# QCopterRC_MCU_Sch.net
KiCad netlist of a schematic drawn in Altium Designer
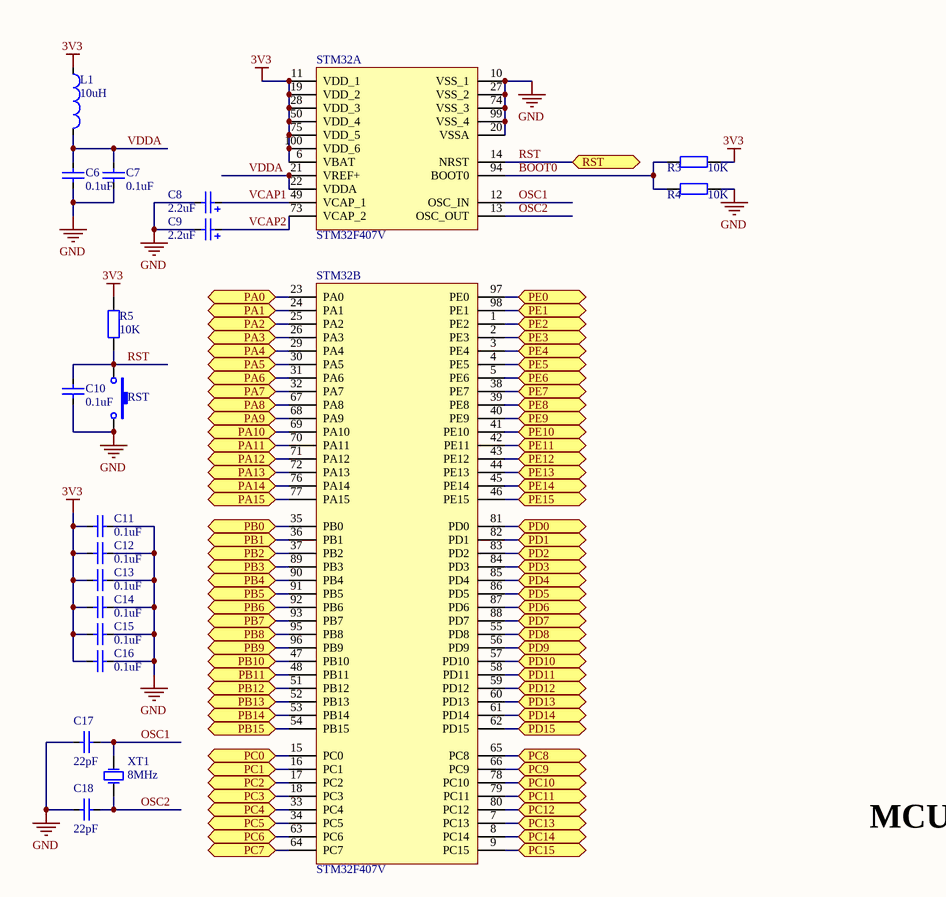
[diagram p0: QCopterRC_MCU_Sch.SchDoc]

(export (version "E")
  (design (tool "Eeschema 10.0.6"))
  (components
    (comp (ref "C6")
      (value "0.1uF")
      (footprint "PCB_Passive:CAP_0603")
      (description "Capacitor")
      (fields (field (name "Comment") "Cap_0603"))
      (libsource (lib "SCH_Passive") (part "Cap_0603"))
    )
    (comp (ref "C7")
      (value "0.1uF")
      (footprint "PCB_Passive:CAP_0603")
      (description "Capacitor")
      (fields (field (name "Comment") "Cap_0603"))
      (libsource (lib "SCH_Passive") (part "Cap_0603"))
    )
    (comp (ref "C8")
      (value "2.2uF")
      (footprint "PCB_Passive:CAP_TAN_P0805")
      (description "Capacitor")
      (fields (field (name "Comment") "Cap_Tan_0805"))
      (libsource (lib "SCH_Passive") (part "Cap_Tan_0805"))
    )
    (comp (ref "C9")
      (value "2.2uF")
      (footprint "PCB_Passive:CAP_TAN_P0805")
      (description "Capacitor")
      (fields (field (name "Comment") "Cap_Tan_0805"))
      (libsource (lib "SCH_Passive") (part "Cap_Tan_0805"))
    )
    (comp (ref "C10")
      (value "0.1uF")
      (footprint "PCB_Passive:CAP_0603")
      (description "Capacitor")
      (fields (field (name "Comment") "Cap_0603"))
      (libsource (lib "SCH_Passive") (part "Cap_0603"))
    )
    (comp (ref "C11")
      (value "0.1uF")
      (footprint "PCB_Passive:CAP_0603")
      (description "Capacitor")
      (fields (field (name "Comment") "Cap_0603"))
      (libsource (lib "SCH_Passive") (part "Cap_0603"))
    )
    (comp (ref "C12")
      (value "0.1uF")
      (footprint "PCB_Passive:CAP_0603")
      (description "Capacitor")
      (fields (field (name "Comment") "Cap_0603"))
      (libsource (lib "SCH_Passive") (part "Cap_0603"))
    )
    (comp (ref "C13")
      (value "0.1uF")
      (footprint "PCB_Passive:CAP_0603")
      (description "Capacitor")
      (fields (field (name "Comment") "Cap_0603"))
      (libsource (lib "SCH_Passive") (part "Cap_0603"))
    )
    (comp (ref "C14")
      (value "0.1uF")
      (footprint "PCB_Passive:CAP_0603")
      (description "Capacitor")
      (fields (field (name "Comment") "Cap_0603"))
      (libsource (lib "SCH_Passive") (part "Cap_0603"))
    )
    (comp (ref "C15")
      (value "0.1uF")
      (footprint "PCB_Passive:CAP_0603")
      (description "Capacitor")
      (fields (field (name "Comment") "Cap_0603"))
      (libsource (lib "SCH_Passive") (part "Cap_0603"))
    )
    (comp (ref "C16")
      (value "0.1uF")
      (footprint "PCB_Passive:CAP_0603")
      (description "Capacitor")
      (fields (field (name "Comment") "Cap_0603"))
      (libsource (lib "SCH_Passive") (part "Cap_0603"))
    )
    (comp (ref "C17")
      (value "22pF")
      (footprint "PCB_Passive:CAP_0603")
      (description "Capacitor")
      (fields (field (name "Comment") "Cap_0603"))
      (libsource (lib "SCH_Passive") (part "Cap_0603"))
    )
    (comp (ref "C18")
      (value "22pF")
      (footprint "PCB_Passive:CAP_0603")
      (description "Capacitor")
      (fields (field (name "Comment") "Cap_0603"))
      (libsource (lib "SCH_Passive") (part "Cap_0603"))
    )
    (comp (ref "L1")
      (value "10uH")
      (footprint "PCB_Passive:IND_0603")
      (description "Inductor")
      (fields (field (name "Comment") "Ind_0603"))
      (libsource (lib "SCH_Passive") (part "Ind_0603"))
    )
    (comp (ref "R3")
      (value "10K")
      (footprint "PCB_Passive:RES_0603")
      (description "Resistor")
      (fields (field (name "Comment") "Res_0603"))
      (libsource (lib "") (part "Res_0603_1"))
    )
    (comp (ref "R4")
      (value "10K")
      (footprint "PCB_Passive:RES_0603")
      (description "Resistor")
      (fields (field (name "Comment") "Res_0603"))
      (libsource (lib "") (part "Res_0603_1"))
    )
    (comp (ref "R5")
      (value "10K")
      (footprint "PCB_Passive:RES_0603")
      (description "Resistor")
      (fields (field (name "Comment") "Res_0603"))
      (libsource (lib "SCH_Passive") (part "Res_0603"))
    )
    (comp (ref "RST")
      (value "BT_TACT_3x6_180")
      (footprint "PCB_Switch:BT_TACT_3x6_180")
      (description "Switch")
      (libsource (lib "SCH_Switch") (part "BT_TACT_3x6_180"))
    )
    (comp (ref "STM32")
      (value "STM32F407V")
      (footprint "PCB_IC:STM32F_100")
      (description "MCU")
      (libsource (lib "SCH_IC") (part "STM32F407V"))
    )
    (comp (ref "XT1")
      (value "8MHz")
      (footprint "PCB_Oscillator:XTAL_5032")
      (description "Crystal Oscillator")
      (fields (field (name "Comment") "XTAL_5032") (field (name "PUBLISHER") "Altium Limited"))
      (libsource (lib "SCH_Oscillator") (part "XTAL_5032"))
    )
  )
  (nets
    (net (code "1") (name "/BOOT0") (class "Default")
      (node (ref "R3") (pin "1") (pinfunction "1_1") (pintype "passive"))
      (node (ref "R4") (pin "1") (pinfunction "1_1") (pintype "passive"))
      (node (ref "STM32") (pin "94") (pinfunction "BOOT0_94") (pintype "passive"))
    )
    (net (code "2") (name "/OSC1") (class "Default")
      (node (ref "C17") (pin "2") (pinfunction "2_2") (pintype "passive"))
      (node (ref "STM32") (pin "12") (pinfunction "OSC_IN_12") (pintype "passive"))
      (node (ref "XT1") (pin "2") (pinfunction "OSC2_2") (pintype "passive"))
    )
    (net (code "3") (name "/OSC2") (class "Default")
      (node (ref "C18") (pin "2") (pinfunction "2_2") (pintype "passive"))
      (node (ref "STM32") (pin "13") (pinfunction "OSC_OUT_13") (pintype "passive"))
      (node (ref "XT1") (pin "1") (pinfunction "OSC1_1") (pintype "passive"))
    )
    (net (code "4") (name "/PA0") (class "Default")
      (node (ref "STM32") (pin "23") (pinfunction "PA0_23") (pintype "passive"))
    )
    (net (code "5") (name "/PA1") (class "Default")
      (node (ref "STM32") (pin "24") (pinfunction "PA1_24") (pintype "passive"))
    )
    (net (code "6") (name "/PA2") (class "Default")
      (node (ref "STM32") (pin "25") (pinfunction "PA2_25") (pintype "passive"))
    )
    (net (code "7") (name "/PA3") (class "Default")
      (node (ref "STM32") (pin "26") (pinfunction "PA3_26") (pintype "passive"))
    )
    (net (code "8") (name "/PA4") (class "Default")
      (node (ref "STM32") (pin "29") (pinfunction "PA4_29") (pintype "passive"))
    )
    (net (code "9") (name "/PA5") (class "Default")
      (node (ref "STM32") (pin "30") (pinfunction "PA5_30") (pintype "passive"))
    )
    (net (code "10") (name "/PA6") (class "Default")
      (node (ref "STM32") (pin "31") (pinfunction "PA6_31") (pintype "passive"))
    )
    (net (code "11") (name "/PA7") (class "Default")
      (node (ref "STM32") (pin "32") (pinfunction "PA7_32") (pintype "passive"))
    )
    (net (code "12") (name "/PA8") (class "Default")
      (node (ref "STM32") (pin "67") (pinfunction "PA8_67") (pintype "passive"))
    )
    (net (code "13") (name "/PA9") (class "Default")
      (node (ref "STM32") (pin "68") (pinfunction "PA9_68") (pintype "passive"))
    )
    (net (code "14") (name "/PA10") (class "Default")
      (node (ref "STM32") (pin "69") (pinfunction "PA10_69") (pintype "passive"))
    )
    (net (code "15") (name "/PA11") (class "Default")
      (node (ref "STM32") (pin "70") (pinfunction "PA11_70") (pintype "passive"))
    )
    (net (code "16") (name "/PA12") (class "Default")
      (node (ref "STM32") (pin "71") (pinfunction "PA12_71") (pintype "passive"))
    )
    (net (code "17") (name "/PA13") (class "Default")
      (node (ref "STM32") (pin "72") (pinfunction "PA13_72") (pintype "passive"))
    )
    (net (code "18") (name "/PA14") (class "Default")
      (node (ref "STM32") (pin "76") (pinfunction "PA14_76") (pintype "passive"))
    )
    (net (code "19") (name "/PA15") (class "Default")
      (node (ref "STM32") (pin "77") (pinfunction "PA15_77") (pintype "passive"))
    )
    (net (code "20") (name "/PB0") (class "Default")
      (node (ref "STM32") (pin "35") (pinfunction "PB0_35") (pintype "passive"))
    )
    (net (code "21") (name "/PB1") (class "Default")
      (node (ref "STM32") (pin "36") (pinfunction "PB1_36") (pintype "passive"))
    )
    (net (code "22") (name "/PB2") (class "Default")
      (node (ref "STM32") (pin "37") (pinfunction "PB2_37") (pintype "passive"))
    )
    (net (code "23") (name "/PB3") (class "Default")
      (node (ref "STM32") (pin "89") (pinfunction "PB3_89") (pintype "passive"))
    )
    (net (code "24") (name "/PB4") (class "Default")
      (node (ref "STM32") (pin "90") (pinfunction "PB4_90") (pintype "passive"))
    )
    (net (code "25") (name "/PB5") (class "Default")
      (node (ref "STM32") (pin "91") (pinfunction "PB5_91") (pintype "passive"))
    )
    (net (code "26") (name "/PB6") (class "Default")
      (node (ref "STM32") (pin "92") (pinfunction "PB6_92") (pintype "passive"))
    )
    (net (code "27") (name "/PB7") (class "Default")
      (node (ref "STM32") (pin "93") (pinfunction "PB7_93") (pintype "passive"))
    )
    (net (code "28") (name "/PB8") (class "Default")
      (node (ref "STM32") (pin "95") (pinfunction "PB8_95") (pintype "passive"))
    )
    (net (code "29") (name "/PB9") (class "Default")
      (node (ref "STM32") (pin "96") (pinfunction "PB9_96") (pintype "passive"))
    )
    (net (code "30") (name "/PB10") (class "Default")
      (node (ref "STM32") (pin "47") (pinfunction "PB10_47") (pintype "passive"))
    )
    (net (code "31") (name "/PB11") (class "Default")
      (node (ref "STM32") (pin "48") (pinfunction "PB11_48") (pintype "passive"))
    )
    (net (code "32") (name "/PB12") (class "Default")
      (node (ref "STM32") (pin "51") (pinfunction "PB12_51") (pintype "passive"))
    )
    (net (code "33") (name "/PB13") (class "Default")
      (node (ref "STM32") (pin "52") (pinfunction "PB13_52") (pintype "passive"))
    )
    (net (code "34") (name "/PB14") (class "Default")
      (node (ref "STM32") (pin "53") (pinfunction "PB14_53") (pintype "passive"))
    )
    (net (code "35") (name "/PB15") (class "Default")
      (node (ref "STM32") (pin "54") (pinfunction "PB15_54") (pintype "passive"))
    )
    (net (code "36") (name "/PC0") (class "Default")
      (node (ref "STM32") (pin "15") (pinfunction "PC0_15") (pintype "passive"))
    )
    (net (code "37") (name "/PC1") (class "Default")
      (node (ref "STM32") (pin "16") (pinfunction "PC1_16") (pintype "passive"))
    )
    (net (code "38") (name "/PC2") (class "Default")
      (node (ref "STM32") (pin "17") (pinfunction "PC2_17") (pintype "passive"))
    )
    (net (code "39") (name "/PC3") (class "Default")
      (node (ref "STM32") (pin "18") (pinfunction "PC3_18") (pintype "passive"))
    )
    (net (code "40") (name "/PC4") (class "Default")
      (node (ref "STM32") (pin "33") (pinfunction "PC4_33") (pintype "passive"))
    )
    (net (code "41") (name "/PC5") (class "Default")
      (node (ref "STM32") (pin "34") (pinfunction "PC5_34") (pintype "passive"))
    )
    (net (code "42") (name "/PC6") (class "Default")
      (node (ref "STM32") (pin "63") (pinfunction "PC6_63") (pintype "passive"))
    )
    (net (code "43") (name "/PC7") (class "Default")
      (node (ref "STM32") (pin "64") (pinfunction "PC7_64") (pintype "passive"))
    )
    (net (code "44") (name "/PC8") (class "Default")
      (node (ref "STM32") (pin "65") (pinfunction "PC8_65") (pintype "passive"))
    )
    (net (code "45") (name "/PC9") (class "Default")
      (node (ref "STM32") (pin "66") (pinfunction "PC9_66") (pintype "passive"))
    )
    (net (code "46") (name "/PC10") (class "Default")
      (node (ref "STM32") (pin "78") (pinfunction "PC10_78") (pintype "passive"))
    )
    (net (code "47") (name "/PC11") (class "Default")
      (node (ref "STM32") (pin "79") (pinfunction "PC11_79") (pintype "passive"))
    )
    (net (code "48") (name "/PC12") (class "Default")
      (node (ref "STM32") (pin "80") (pinfunction "PC12_80") (pintype "passive"))
    )
    (net (code "49") (name "/PC13") (class "Default")
      (node (ref "STM32") (pin "7") (pinfunction "PC13_7") (pintype "passive"))
    )
    (net (code "50") (name "/PC14") (class "Default")
      (node (ref "STM32") (pin "8") (pinfunction "PC14_8") (pintype "passive"))
    )
    (net (code "51") (name "/PC15") (class "Default")
      (node (ref "STM32") (pin "9") (pinfunction "PC15_9") (pintype "passive"))
    )
    (net (code "52") (name "/PD0") (class "Default")
      (node (ref "STM32") (pin "81") (pinfunction "PD0_81") (pintype "passive"))
    )
    (net (code "53") (name "/PD1") (class "Default")
      (node (ref "STM32") (pin "82") (pinfunction "PD1_82") (pintype "passive"))
    )
    (net (code "54") (name "/PD2") (class "Default")
      (node (ref "STM32") (pin "83") (pinfunction "PD2_83") (pintype "passive"))
    )
    (net (code "55") (name "/PD3") (class "Default")
      (node (ref "STM32") (pin "84") (pinfunction "PD3_84") (pintype "passive"))
    )
    (net (code "56") (name "/PD4") (class "Default")
      (node (ref "STM32") (pin "85") (pinfunction "PD4_85") (pintype "passive"))
    )
    (net (code "57") (name "/PD5") (class "Default")
      (node (ref "STM32") (pin "86") (pinfunction "PD5_86") (pintype "passive"))
    )
    (net (code "58") (name "/PD6") (class "Default")
      (node (ref "STM32") (pin "87") (pinfunction "PD6_87") (pintype "passive"))
    )
    (net (code "59") (name "/PD7") (class "Default")
      (node (ref "STM32") (pin "88") (pinfunction "PD7_88") (pintype "passive"))
    )
    (net (code "60") (name "/PD8") (class "Default")
      (node (ref "STM32") (pin "55") (pinfunction "PD8_55") (pintype "passive"))
    )
    (net (code "61") (name "/PD9") (class "Default")
      (node (ref "STM32") (pin "56") (pinfunction "PD9_56") (pintype "passive"))
    )
    (net (code "62") (name "/PD10") (class "Default")
      (node (ref "STM32") (pin "57") (pinfunction "PD10_57") (pintype "passive"))
    )
    (net (code "63") (name "/PD11") (class "Default")
      (node (ref "STM32") (pin "58") (pinfunction "PD11_58") (pintype "passive"))
    )
    (net (code "64") (name "/PD12") (class "Default")
      (node (ref "STM32") (pin "59") (pinfunction "PD12_59") (pintype "passive"))
    )
    (net (code "65") (name "/PD13") (class "Default")
      (node (ref "STM32") (pin "60") (pinfunction "PD13_60") (pintype "passive"))
    )
    (net (code "66") (name "/PD14") (class "Default")
      (node (ref "STM32") (pin "61") (pinfunction "PD14_61") (pintype "passive"))
    )
    (net (code "67") (name "/PD15") (class "Default")
      (node (ref "STM32") (pin "62") (pinfunction "PD15_62") (pintype "passive"))
    )
    (net (code "68") (name "/PE0") (class "Default")
      (node (ref "STM32") (pin "97") (pinfunction "PE0_97") (pintype "passive"))
    )
    (net (code "69") (name "/PE1") (class "Default")
      (node (ref "STM32") (pin "98") (pinfunction "PE1_98") (pintype "passive"))
    )
    (net (code "70") (name "/PE2") (class "Default")
      (node (ref "STM32") (pin "1") (pinfunction "PE2_1") (pintype "passive"))
    )
    (net (code "71") (name "/PE3") (class "Default")
      (node (ref "STM32") (pin "2") (pinfunction "PE3_2") (pintype "passive"))
    )
    (net (code "72") (name "/PE4") (class "Default")
      (node (ref "STM32") (pin "3") (pinfunction "PE4_3") (pintype "passive"))
    )
    (net (code "73") (name "/PE5") (class "Default")
      (node (ref "STM32") (pin "4") (pinfunction "PE5_4") (pintype "passive"))
    )
    (net (code "74") (name "/PE6") (class "Default")
      (node (ref "STM32") (pin "5") (pinfunction "PE6_5") (pintype "passive"))
    )
    (net (code "75") (name "/PE7") (class "Default")
      (node (ref "STM32") (pin "38") (pinfunction "PE7_38") (pintype "passive"))
    )
    (net (code "76") (name "/PE8") (class "Default")
      (node (ref "STM32") (pin "39") (pinfunction "PE8_39") (pintype "passive"))
    )
    (net (code "77") (name "/PE9") (class "Default")
      (node (ref "STM32") (pin "40") (pinfunction "PE9_40") (pintype "passive"))
    )
    (net (code "78") (name "/PE10") (class "Default")
      (node (ref "STM32") (pin "41") (pinfunction "PE10_41") (pintype "passive"))
    )
    (net (code "79") (name "/PE11") (class "Default")
      (node (ref "STM32") (pin "42") (pinfunction "PE11_42") (pintype "passive"))
    )
    (net (code "80") (name "/PE12") (class "Default")
      (node (ref "STM32") (pin "43") (pinfunction "PE12_43") (pintype "passive"))
    )
    (net (code "81") (name "/PE13") (class "Default")
      (node (ref "STM32") (pin "44") (pinfunction "PE13_44") (pintype "passive"))
    )
    (net (code "82") (name "/PE14") (class "Default")
      (node (ref "STM32") (pin "45") (pinfunction "PE14_45") (pintype "passive"))
    )
    (net (code "83") (name "/PE15") (class "Default")
      (node (ref "STM32") (pin "46") (pinfunction "PE15_46") (pintype "passive"))
    )
    (net (code "84") (name "/RST") (class "Default")
      (node (ref "C10") (pin "1") (pinfunction "1_1") (pintype "passive"))
      (node (ref "R5") (pin "2") (pinfunction "2_2") (pintype "passive"))
      (node (ref "RST") (pin "1") (pinfunction "1_1") (pintype "passive"))
      (node (ref "STM32") (pin "14") (pinfunction "NRST_14") (pintype "passive"))
    )
    (net (code "85") (name "/VCAP1") (class "Default")
      (node (ref "C8") (pin "1") (pinfunction "1_1") (pintype "passive"))
      (node (ref "STM32") (pin "49") (pinfunction "VCAP_1_49") (pintype "passive"))
    )
    (net (code "86") (name "/VCAP2") (class "Default")
      (node (ref "C9") (pin "1") (pinfunction "1_1") (pintype "passive"))
      (node (ref "STM32") (pin "73") (pinfunction "VCAP_2_73") (pintype "passive"))
    )
    (net (code "87") (name "/VDDA") (class "Default")
      (node (ref "C6") (pin "1") (pinfunction "1_1") (pintype "passive"))
      (node (ref "C7") (pin "1") (pinfunction "1_1") (pintype "passive"))
      (node (ref "L1") (pin "2") (pinfunction "2_2") (pintype "passive"))
      (node (ref "STM32") (pin "21") (pinfunction "VREF+_21") (pintype "passive"))
      (node (ref "STM32") (pin "22") (pinfunction "VDDA_22") (pintype "passive"))
    )
    (net (code "88") (name "3V3") (class "Default")
      (node (ref "C11") (pin "2") (pinfunction "2_2") (pintype "passive"))
      (node (ref "C12") (pin "2") (pinfunction "2_2") (pintype "passive"))
      (node (ref "C13") (pin "2") (pinfunction "2_2") (pintype "passive"))
      (node (ref "C14") (pin "2") (pinfunction "2_2") (pintype "passive"))
      (node (ref "C15") (pin "2") (pinfunction "2_2") (pintype "passive"))
      (node (ref "C16") (pin "2") (pinfunction "2_2") (pintype "passive"))
      (node (ref "L1") (pin "1") (pinfunction "1_1") (pintype "passive"))
      (node (ref "R3") (pin "2") (pinfunction "2_2") (pintype "passive"))
      (node (ref "R5") (pin "1") (pinfunction "1_1") (pintype "passive"))
      (node (ref "STM32") (pin "100") (pinfunction "VDD_6_100") (pintype "passive"))
      (node (ref "STM32") (pin "11") (pinfunction "VDD_1_11") (pintype "passive"))
      (node (ref "STM32") (pin "19") (pinfunction "VDD_2_19") (pintype "passive"))
      (node (ref "STM32") (pin "28") (pinfunction "VDD_3_28") (pintype "passive"))
      (node (ref "STM32") (pin "50") (pinfunction "VDD_4_50") (pintype "passive"))
      (node (ref "STM32") (pin "6") (pinfunction "VBAT_6") (pintype "passive"))
      (node (ref "STM32") (pin "75") (pinfunction "VDD_5_75") (pintype "passive"))
    )
    (net (code "89") (name "GND") (class "Default")
      (node (ref "C10") (pin "2") (pinfunction "2_2") (pintype "passive"))
      (node (ref "C11") (pin "1") (pinfunction "1_1") (pintype "passive"))
      (node (ref "C12") (pin "1") (pinfunction "1_1") (pintype "passive"))
      (node (ref "C13") (pin "1") (pinfunction "1_1") (pintype "passive"))
      (node (ref "C14") (pin "1") (pinfunction "1_1") (pintype "passive"))
      (node (ref "C15") (pin "1") (pinfunction "1_1") (pintype "passive"))
      (node (ref "C16") (pin "1") (pinfunction "1_1") (pintype "passive"))
      (node (ref "C17") (pin "1") (pinfunction "1_1") (pintype "passive"))
      (node (ref "C18") (pin "1") (pinfunction "1_1") (pintype "passive"))
      (node (ref "C6") (pin "2") (pinfunction "2_2") (pintype "passive"))
      (node (ref "C7") (pin "2") (pinfunction "2_2") (pintype "passive"))
      (node (ref "C8") (pin "2") (pinfunction "2_2") (pintype "passive"))
      (node (ref "C9") (pin "2") (pinfunction "2_2") (pintype "passive"))
      (node (ref "R4") (pin "2") (pinfunction "2_2") (pintype "passive"))
      (node (ref "RST") (pin "2") (pinfunction "2_2") (pintype "passive"))
      (node (ref "STM32") (pin "10") (pinfunction "VSS_1_10") (pintype "passive"))
      (node (ref "STM32") (pin "20") (pinfunction "VSSA_20") (pintype "passive"))
      (node (ref "STM32") (pin "27") (pinfunction "VSS_2_27") (pintype "passive"))
      (node (ref "STM32") (pin "74") (pinfunction "VSS_3_74") (pintype "passive"))
      (node (ref "STM32") (pin "99") (pinfunction "VSS_4_99") (pintype "passive"))
    )
  )
)
